# Voltage_Bridge.net
KiCad netlist of a schematic drawn in Altium Designer
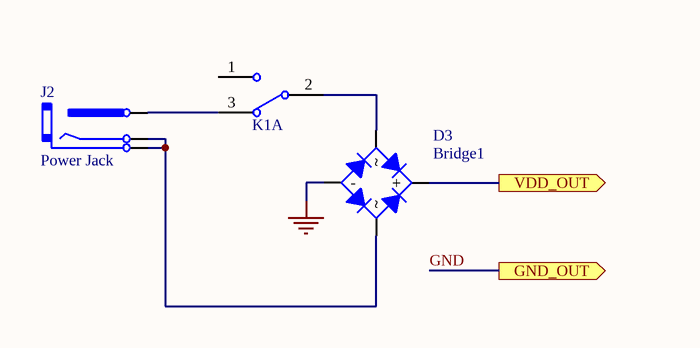
[diagram p0: Voltage_Bridge.SchDoc]

(export (version "E")
  (design (tool "Eeschema 10.0.6"))
  (components
    (comp (ref "D3")
      (value "Bridge1")
      (footprint "BRIDGE-2")
      (description "Full Wave Diode Bridge")
      (fields (field (name "MANUFACTURER") "Generic Components") (field (name "PUBLISHER") "Altium Limited"))
      (libsource (lib "Miscellaneous Devices") (part "Bridge1"))
    )
    (comp (ref "J2")
      (value "Power Jack")
      (footprint "KLD-0202")
      (libsource (lib "Miscellaneous Devices") (part "Power Jack"))
    )
    (comp (ref "K1")
      (value "SW DPDT_2")
      (footprint "DPDT-6_2")
      (description "Single-Pole, Double-Throw Switch, Key")
      (fields (field (name "MANUFACTURER") "Generic Components") (field (name "PUBLISHER") "Altium Limited"))
      (libsource (lib "Miscellaneous Devices") (part "SW DPDT_2"))
    )
  )
  (nets
    (net (code "1") (name "/VDD_OUT") (class "Default")
      (node (ref "D3") (pin "3") (pinfunction "+_3") (pintype "passive"))
    )
    (net (code "2") (name "GND") (class "Default")
      (node (ref "D3") (pin "1") (pinfunction "-_1") (pintype "passive"))
    )
    (net (code "3") (name "Net-(J2-B)") (class "Default")
      (node (ref "D3") (pin "4") (pinfunction "~_4") (pintype "passive"))
      (node (ref "J2") (pin "2") (pinfunction "A_2") (pintype "passive"))
      (node (ref "J2") (pin "3") (pinfunction "B_3") (pintype "passive"))
    )
    (net (code "4") (name "Net-(K1A-COMMON)") (class "Default")
      (node (ref "D3") (pin "2") (pinfunction "~_2") (pintype "passive"))
      (node (ref "K1") (pin "2") (pinfunction "COMMON_2") (pintype "passive"))
    )
    (net (code "5") (name "Net-(K1A-NC)") (class "Default")
      (node (ref "J2") (pin "1") (pinfunction "A_1") (pintype "passive"))
      (node (ref "K1") (pin "3") (pinfunction "NC_3") (pintype "passive"))
    )
    (net (code "6") (name "unconnected-(K1A-NO-Pad1)") (class "Default")
      (node (ref "K1") (pin "1") (pinfunction "NO_1") (pintype "passive"))
    )
  )
)
